# Module_20200402_0_ServoAdapter.net
KiCad netlist of a schematic drawn in EAGLE
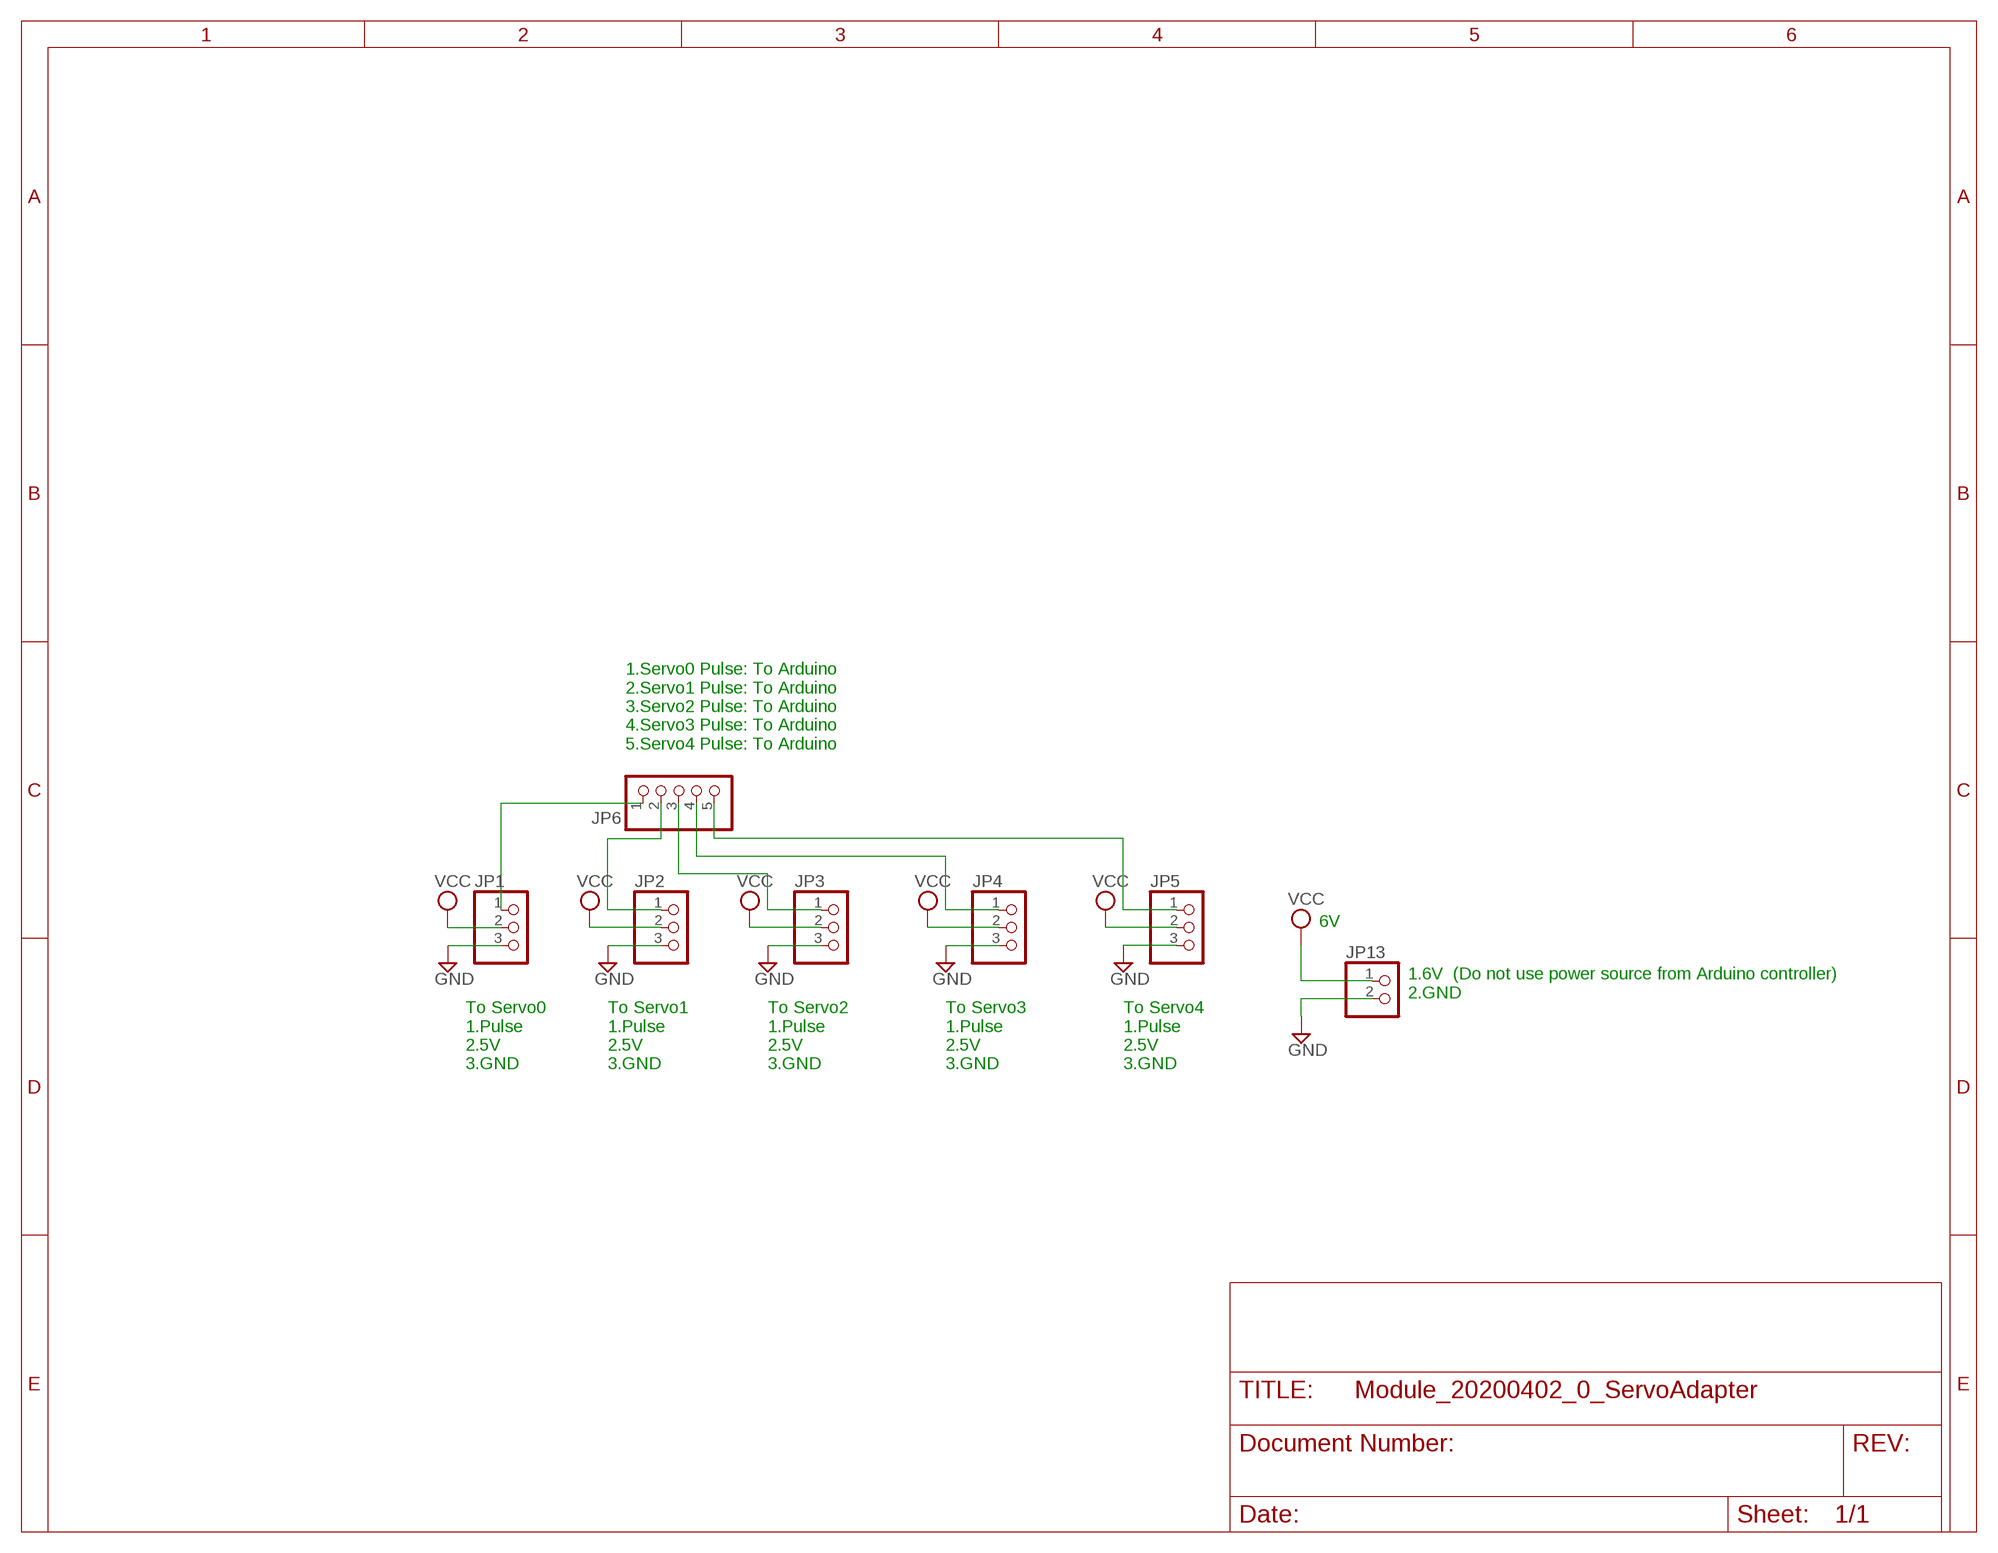
[diagram p0: schematic, sheet 1]

(export (version "E")
  (design (tool "Eeschema 10.0.6"))
  (components
    (comp (ref "JP1")
      (value "PINHD-1X3")
      (footprint "eagle-import:1X03")
      (libsource (lib "eagle-import") (part "PINHD-1X3"))
    )
    (comp (ref "JP2")
      (value "PINHD-1X3")
      (footprint "eagle-import:1X03")
      (libsource (lib "eagle-import") (part "PINHD-1X3"))
    )
    (comp (ref "JP3")
      (value "PINHD-1X3")
      (footprint "eagle-import:1X03")
      (libsource (lib "eagle-import") (part "PINHD-1X3"))
    )
    (comp (ref "JP4")
      (value "PINHD-1X3")
      (footprint "eagle-import:1X03")
      (libsource (lib "eagle-import") (part "PINHD-1X3"))
    )
    (comp (ref "JP5")
      (value "PINHD-1X3")
      (footprint "eagle-import:1X03")
      (libsource (lib "eagle-import") (part "PINHD-1X3"))
    )
    (comp (ref "JP6")
      (value "PINHD-1X5")
      (footprint "eagle-import:1X05")
      (libsource (lib "eagle-import") (part "PINHD-1X5"))
    )
    (comp (ref "JP13")
      (value "PINHD-1X2")
      (footprint "eagle-import:1X02")
      (libsource (lib "eagle-import") (part "PINHD-1X2"))
    )
  )
  (nets
    (net (code "1") (name "GND") (class "Default")
      (node (ref "JP1") (pin "3") (pinfunction "3_3") (pintype "passive"))
      (node (ref "JP13") (pin "2") (pinfunction "2_2") (pintype "passive"))
      (node (ref "JP2") (pin "3") (pinfunction "3_3") (pintype "passive"))
      (node (ref "JP3") (pin "3") (pinfunction "3_3") (pintype "passive"))
      (node (ref "JP4") (pin "3") (pinfunction "3_3") (pintype "passive"))
      (node (ref "JP5") (pin "3") (pinfunction "3_3") (pintype "passive"))
    )
    (net (code "2") (name "Net-(JP1-Pad1)") (class "Default")
      (node (ref "JP1") (pin "1") (pinfunction "1_1") (pintype "passive"))
      (node (ref "JP6") (pin "1") (pinfunction "1_1") (pintype "passive"))
    )
    (net (code "3") (name "Net-(JP2-Pad1)") (class "Default")
      (node (ref "JP2") (pin "1") (pinfunction "1_1") (pintype "passive"))
      (node (ref "JP6") (pin "2") (pinfunction "2_2") (pintype "passive"))
    )
    (net (code "4") (name "Net-(JP3-Pad1)") (class "Default")
      (node (ref "JP3") (pin "1") (pinfunction "1_1") (pintype "passive"))
      (node (ref "JP6") (pin "3") (pinfunction "3_3") (pintype "passive"))
    )
    (net (code "5") (name "Net-(JP4-Pad1)") (class "Default")
      (node (ref "JP4") (pin "1") (pinfunction "1_1") (pintype "passive"))
      (node (ref "JP6") (pin "4") (pinfunction "4_4") (pintype "passive"))
    )
    (net (code "6") (name "Net-(JP5-Pad1)") (class "Default")
      (node (ref "JP5") (pin "1") (pinfunction "1_1") (pintype "passive"))
      (node (ref "JP6") (pin "5") (pinfunction "5_5") (pintype "passive"))
    )
    (net (code "7") (name "VCC") (class "Default")
      (node (ref "JP1") (pin "2") (pinfunction "2_2") (pintype "passive"))
      (node (ref "JP13") (pin "1") (pinfunction "1_1") (pintype "passive"))
      (node (ref "JP2") (pin "2") (pinfunction "2_2") (pintype "passive"))
      (node (ref "JP3") (pin "2") (pinfunction "2_2") (pintype "passive"))
      (node (ref "JP4") (pin "2") (pinfunction "2_2") (pintype "passive"))
      (node (ref "JP5") (pin "2") (pinfunction "2_2") (pintype "passive"))
    )
  )
)
